# 1_P1.net
KiCad netlist of a schematic drawn in Altium Designer
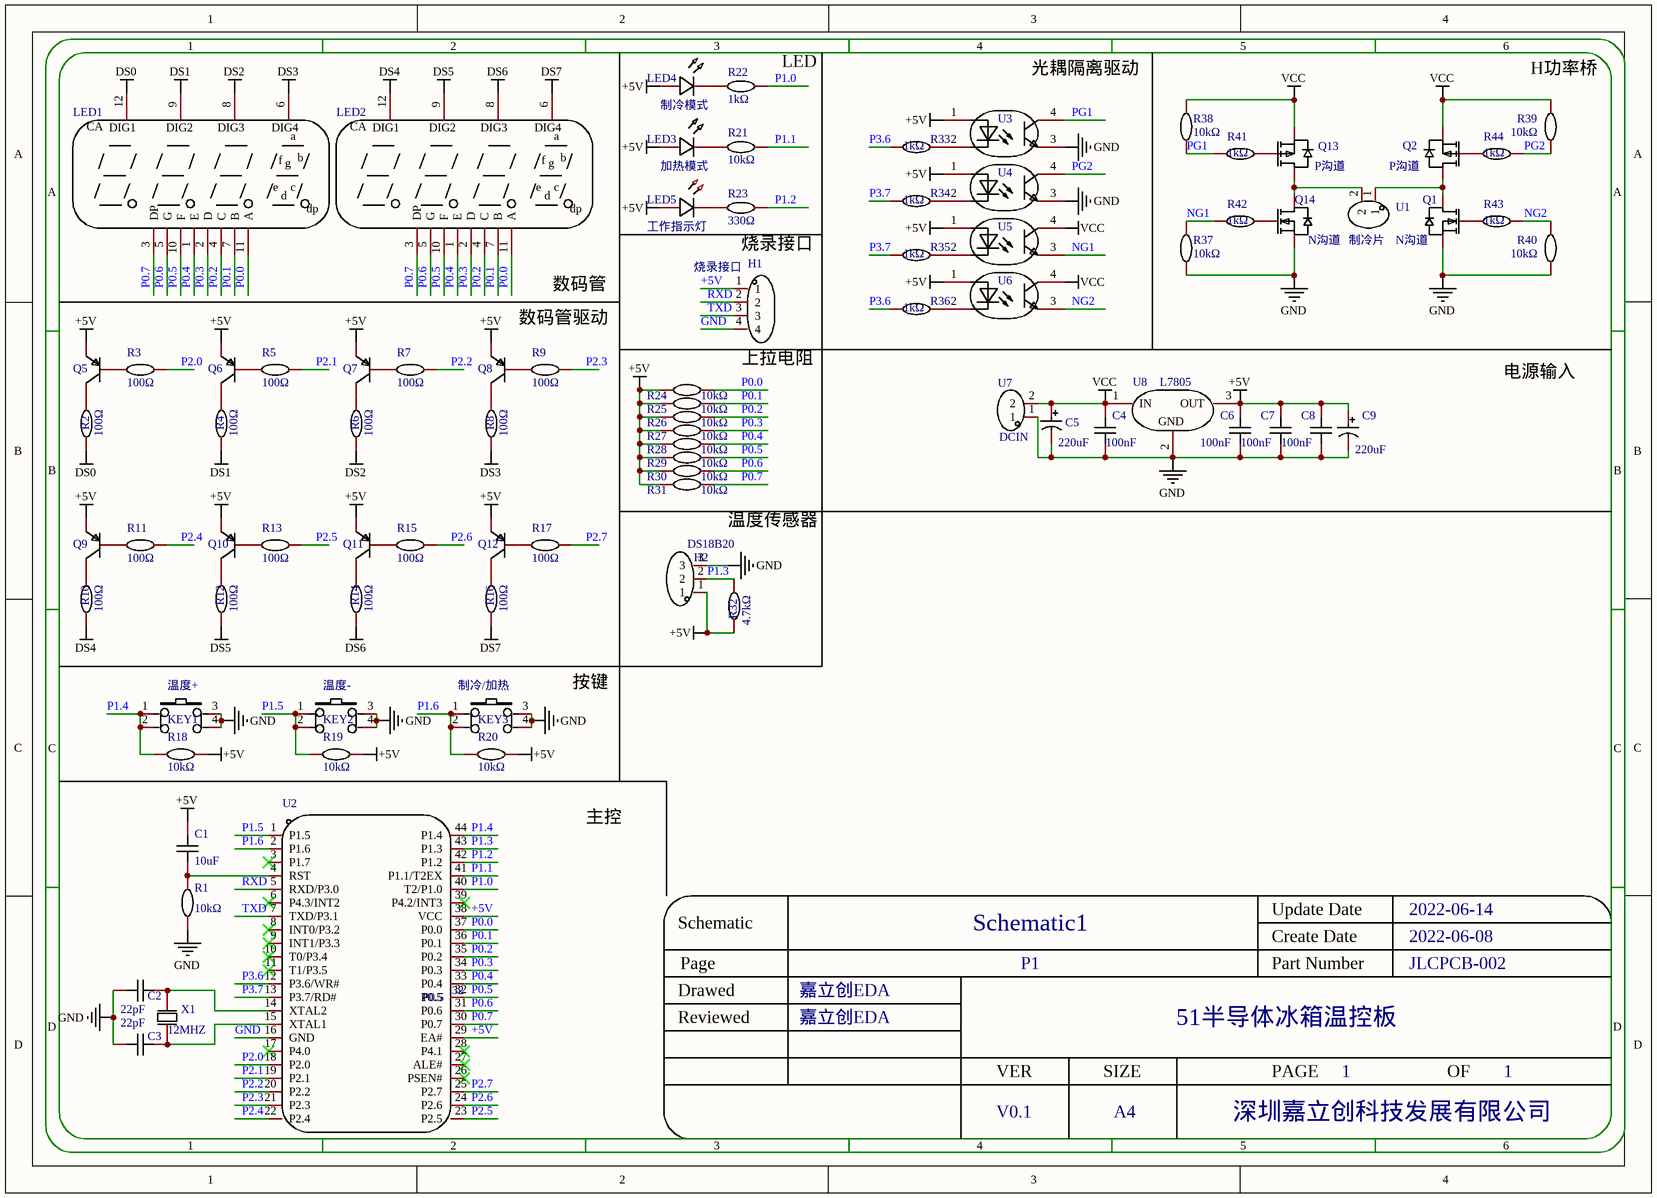
[diagram p0: 1_P1.schdoc]

(export (version "E")
  (design (tool "Eeschema 10.0.6"))
  (components
    (comp (ref "C1")
      (value "10uF")
      (footprint "C0805")
      (description "容值:100nF;精度:±10%;额定电压:50V;温度系数:X7R;")
      (fields (field (name "Comment") "CAP_0805"))
      (libsource (lib "altium-import") (part "root_1_CAP_0805_"))
    )
    (comp (ref "C2")
      (value "22pF")
      (footprint "C0805")
      (description "容值:100nF;精度:±10%;额定电压:50V;温度系数:X7R;")
      (fields (field (name "Comment") "CAP_0805"))
      (libsource (lib "altium-import") (part "root_0_CAP_0805_"))
    )
    (comp (ref "C3")
      (value "22pF")
      (footprint "C0805")
      (description "容值:100nF;精度:±10%;额定电压:50V;温度系数:X7R;")
      (fields (field (name "Comment") "CAP_0805"))
      (libsource (lib "altium-import") (part "root_0_CAP_0805_"))
    )
    (comp (ref "C4")
      (value "C318C362K5G5TA")
      (footprint "CAP-TH_L3.8-W2.5-P5.08-D0.5")
      (fields (field (name "MANUFACTURER") "KEMET(基美)") (field (name "CAPACITANCE") "100nF"))
      (libsource (lib "altium-import") (part "root_1_C318C362K5G5TA_"))
    )
    (comp (ref "C5")
      (value "220uF")
      (footprint "CAP-TH_BD6.3-P2.50-D1.0-FD")
      (description "容值:220uF;精度:±20%;额定电压:10V;电容体直径:6.3mm;电容体长度:7mm;脚间距:2.5mm;纹波电流:-;等效串联电阻:-;工作寿命:1000hrs@105;工作温度:-;")
      (fields
        (field (name "MANUFACTURER") "CapXon(台湾丰宾)")
        (field (name "MANUFACTURER PART") "SK221M010E070A")
      )
      (libsource (lib "altium-import") (part "root_3_SK221M010E070A_"))
    )
    (comp (ref "C6")
      (value "100nF")
      (footprint "C0805")
      (description "容值:100nF;精度:±10%;额定电压:50V;温度系数:X7R;")
      (fields (field (name "Comment") "CAP_0805"))
      (libsource (lib "altium-import") (part "root_1_CAP_0805_"))
    )
    (comp (ref "C7")
      (value "100nF")
      (footprint "C0805")
      (description "容值:100nF;精度:±10%;额定电压:50V;温度系数:X7R;")
      (fields (field (name "Comment") "CAP_0805"))
      (libsource (lib "altium-import") (part "root_1_CAP_0805_"))
    )
    (comp (ref "C8")
      (value "100nF")
      (footprint "C0805")
      (description "容值:100nF;精度:±10%;额定电压:50V;温度系数:X7R;")
      (fields (field (name "Comment") "CAP_0805"))
      (libsource (lib "altium-import") (part "root_1_CAP_0805_"))
    )
    (comp (ref "C9")
      (value "220uF")
      (footprint "CAP-TH_BD6.3-P2.50-D1.0-FD")
      (description "容值:220uF;精度:±20%;额定电压:10V;电容体直径:6.3mm;电容体长度:7mm;脚间距:2.5mm;纹波电流:-;等效串联电阻:-;工作寿命:1000hrs@105;工作温度:-;")
      (fields
        (field (name "MANUFACTURER") "CapXon(台湾丰宾)")
        (field (name "MANUFACTURER PART") "SK221M010E070A")
      )
      (libsource (lib "altium-import") (part "root_3_SK221M010E070A_"))
    )
    (comp (ref "H1")
      (value "烧录接口")
      (footprint "HDR-TH_4P-P2.54-V-F")
      (fields (field (name "NAME") "烧录接口"))
      (libsource (lib "altium-import") (part "root_0_HDR-F_2.54_1x4P_"))
    )
    (comp (ref "H2")
      (value "DS18B20")
      (footprint "HDR-TH_3P-P2.54-V-F")
      (fields (field (name "NAME") "DS18B20"))
      (libsource (lib "altium-import") (part "root_2_HDR-F_2.54_1x3P_"))
    )
    (comp (ref "KEY1")
      (value "温度+")
      (footprint "KEY-SMD_4P-L6.0-W6.0-P4.50")
      (description "触点电流:50mA;额定电压(DC):24V;电路结构:单刀单掷;安装方式:立贴;按钮形状:圆形按钮;带灯:-;开关长度:6mm;开关宽度:6mm;开关高度:5mm;")
      (fields
        (field (name "NAME") "温度+")
        (field (name "MANUFACTURER") "TE Connectivity(美国泰科)")
        (field (name "MANUFACTURER PART") "4-1437565-2")
      )
      (libsource (lib "altium-import") (part "root_0_4-1437565-2_"))
    )
    (comp (ref "KEY2")
      (value "温度-")
      (footprint "KEY-SMD_4P-L6.0-W6.0-P4.50")
      (description "触点电流:50mA;额定电压(DC):24V;电路结构:单刀单掷;安装方式:立贴;按钮形状:圆形按钮;带灯:-;开关长度:6mm;开关宽度:6mm;开关高度:5mm;")
      (fields
        (field (name "NAME") "温度-")
        (field (name "MANUFACTURER") "TE Connectivity(美国泰科)")
        (field (name "MANUFACTURER PART") "4-1437565-2")
      )
      (libsource (lib "altium-import") (part "root_0_4-1437565-2_"))
    )
    (comp (ref "KEY3")
      (value "制冷/加热")
      (footprint "KEY-SMD_4P-L6.0-W6.0-P4.50")
      (description "触点电流:50mA;额定电压(DC):24V;电路结构:单刀单掷;安装方式:立贴;按钮形状:圆形按钮;带灯:-;开关长度:6mm;开关宽度:6mm;开关高度:5mm;")
      (fields
        (field (name "NAME") "制冷/加热")
        (field (name "MANUFACTURER") "TE Connectivity(美国泰科)")
        (field (name "MANUFACTURER PART") "4-1437565-2")
      )
      (libsource (lib "altium-import") (part "root_0_4-1437565-2_"))
    )
    (comp (ref "LED1")
      (value "FJ5461BH 纯红")
      (footprint "LED-SEG-TH_FJ5461AH")
      (description "数码管位数:4;数码管的显示尺寸:0.56''(14.22mm);电路连线类型:阳极(正极);照明颜色:红色;")
      (fields (field (name "MANUFACTURER") "志浩"))
      (libsource (lib "altium-import") (part "root_0_FJ5461BH 纯红_"))
    )
    (comp (ref "LED2")
      (value "FJ5461BH 纯红")
      (footprint "LED-SEG-TH_FJ5461AH")
      (description "数码管位数:4;数码管的显示尺寸:0.56''(14.22mm);电路连线类型:阳极(正极);照明颜色:红色;")
      (fields (field (name "MANUFACTURER") "志浩"))
      (libsource (lib "altium-import") (part "root_0_FJ5461BH 纯红_"))
    )
    (comp (ref "LED3")
      (value "加热模式")
      (footprint "LED-TH_BD3.0-P2.54-FD")
      (fields (field (name "NAME") "加热模式"))
      (libsource (lib "altium-import") (part "root_0_LED_TH-R_3mm_"))
    )
    (comp (ref "LED4")
      (value "制冷模式")
      (footprint "LED-TH_BD3.8-P2.54-FD_BLUE")
      (fields (field (name "NAME") "制冷模式"))
      (libsource (lib "altium-import") (part "root_0_LED_TH-B_3mm_"))
    )
    (comp (ref "LED5")
      (value "工作指示灯")
      (footprint "LED-TH_BD3.0-P2.54-FD")
      (fields (field (name "NAME") "工作指示灯"))
      (libsource (lib "altium-import") (part "root_0_LED_TH-G_3mm_"))
    )
    (comp (ref "Q1")
      (value "N沟道")
      (footprint "TO-220-3_L10.0-W4.5-P2.54-L")
      (fields
        (field (name "NAME") "N沟道")
        (field (name "MANUFACTURER") "CRMICRO(华润微)")
        (field (name "MANUFACTURER PART") "CRST060N10N")
      )
      (libsource (lib "altium-import") (part "root_0_mirrored_CRST060N10N_"))
    )
    (comp (ref "Q2")
      (value "P沟道")
      (footprint "TO-220-3_L10.0-W4.5-P2.54-L")
      (fields
        (field (name "NAME") "P沟道")
        (field (name "MANUFACTURER") "HUASHUO(华朔)")
        (field (name "MANUFACTURER PART") "HSP0115")
      )
      (libsource (lib "altium-import") (part "root_2_HSP0115_"))
    )
    (comp (ref "Q5")
      (value "S8550")
      (footprint "SOT-23-3_L2.9-W1.3-P1.90-LS2.4-BR")
      (fields (field (name "MANUFACTURER") "JSMSEMI(杰盛微)"))
      (libsource (lib "altium-import") (part "root_2_S8550_"))
    )
    (comp (ref "Q6")
      (value "S8550")
      (footprint "SOT-23-3_L2.9-W1.3-P1.90-LS2.4-BR")
      (fields (field (name "MANUFACTURER") "JSMSEMI(杰盛微)"))
      (libsource (lib "altium-import") (part "root_2_S8550_"))
    )
    (comp (ref "Q7")
      (value "S8550")
      (footprint "SOT-23-3_L2.9-W1.3-P1.90-LS2.4-BR")
      (fields (field (name "MANUFACTURER") "JSMSEMI(杰盛微)"))
      (libsource (lib "altium-import") (part "root_2_S8550_"))
    )
    (comp (ref "Q8")
      (value "S8550")
      (footprint "SOT-23-3_L2.9-W1.3-P1.90-LS2.4-BR")
      (fields (field (name "MANUFACTURER") "JSMSEMI(杰盛微)"))
      (libsource (lib "altium-import") (part "root_2_S8550_"))
    )
    (comp (ref "Q9")
      (value "S8550")
      (footprint "SOT-23-3_L2.9-W1.3-P1.90-LS2.4-BR")
      (fields (field (name "MANUFACTURER") "JSMSEMI(杰盛微)"))
      (libsource (lib "altium-import") (part "root_2_S8550_"))
    )
    (comp (ref "Q10")
      (value "S8550")
      (footprint "SOT-23-3_L2.9-W1.3-P1.90-LS2.4-BR")
      (fields (field (name "MANUFACTURER") "JSMSEMI(杰盛微)"))
      (libsource (lib "altium-import") (part "root_2_S8550_"))
    )
    (comp (ref "Q11")
      (value "S8550")
      (footprint "SOT-23-3_L2.9-W1.3-P1.90-LS2.4-BR")
      (fields (field (name "MANUFACTURER") "JSMSEMI(杰盛微)"))
      (libsource (lib "altium-import") (part "root_2_S8550_"))
    )
    (comp (ref "Q12")
      (value "S8550")
      (footprint "SOT-23-3_L2.9-W1.3-P1.90-LS2.4-BR")
      (fields (field (name "MANUFACTURER") "JSMSEMI(杰盛微)"))
      (libsource (lib "altium-import") (part "root_2_S8550_"))
    )
    (comp (ref "Q13")
      (value "P沟道")
      (footprint "TO-220-3_L10.0-W4.5-P2.54-L")
      (fields
        (field (name "NAME") "P沟道")
        (field (name "MANUFACTURER") "HUASHUO(华朔)")
        (field (name "MANUFACTURER PART") "HSP0115")
      )
      (libsource (lib "altium-import") (part "root_2_mirrored_HSP0115_"))
    )
    (comp (ref "Q14")
      (value "N沟道")
      (footprint "TO-220-3_L10.0-W4.5-P2.54-L")
      (fields
        (field (name "NAME") "N沟道")
        (field (name "MANUFACTURER") "CRMICRO(华润微)")
        (field (name "MANUFACTURER PART") "CRST060N10N")
      )
      (libsource (lib "altium-import") (part "root_0_CRST060N10N_"))
    )
    (comp (ref "R1")
      (value "10kΩ")
      (footprint "R0805")
      (description "电阻类型:薄膜电阻;阻值:10kΩ;精度:±0.5%;功率:125mW;温度系数:±25ppm/;最大工作电压:100V;工作温度范围:-55~+155;")
      (fields (field (name "MANUFACTURER") "光颉(Viking)") (field (name "MANUFACTURER PART") "AR05DTCW1002"))
      (libsource (lib "altium-import") (part "root_1_Res_0805_"))
    )
    (comp (ref "R2")
      (value "100Ω")
      (footprint "R0805")
      (description "电阻类型:薄膜电阻;阻值:10kΩ;精度:±0.5%;功率:125mW;温度系数:±25ppm/;最大工作电压:100V;工作温度范围:-55~+155;")
      (fields (field (name "MANUFACTURER") "光颉(Viking)") (field (name "MANUFACTURER PART") "AR05DTCW1002"))
      (libsource (lib "altium-import") (part "root_1_Res_0805_"))
    )
    (comp (ref "R3")
      (value "100Ω")
      (footprint "R0805")
      (description "电阻类型:薄膜电阻;阻值:10kΩ;精度:±0.5%;功率:125mW;温度系数:±25ppm/;最大工作电压:100V;工作温度范围:-55~+155;")
      (fields (field (name "MANUFACTURER") "光颉(Viking)") (field (name "MANUFACTURER PART") "AR05DTCW1002"))
      (libsource (lib "altium-import") (part "root_0_Res_0805_"))
    )
    (comp (ref "R4")
      (value "100Ω")
      (footprint "R0805")
      (description "电阻类型:薄膜电阻;阻值:10kΩ;精度:±0.5%;功率:125mW;温度系数:±25ppm/;最大工作电压:100V;工作温度范围:-55~+155;")
      (fields (field (name "MANUFACTURER") "光颉(Viking)") (field (name "MANUFACTURER PART") "AR05DTCW1002"))
      (libsource (lib "altium-import") (part "root_1_Res_0805_"))
    )
    (comp (ref "R5")
      (value "100Ω")
      (footprint "R0805")
      (description "电阻类型:薄膜电阻;阻值:10kΩ;精度:±0.5%;功率:125mW;温度系数:±25ppm/;最大工作电压:100V;工作温度范围:-55~+155;")
      (fields (field (name "MANUFACTURER") "光颉(Viking)") (field (name "MANUFACTURER PART") "AR05DTCW1002"))
      (libsource (lib "altium-import") (part "root_0_Res_0805_"))
    )
    (comp (ref "R6")
      (value "100Ω")
      (footprint "R0805")
      (description "电阻类型:薄膜电阻;阻值:10kΩ;精度:±0.5%;功率:125mW;温度系数:±25ppm/;最大工作电压:100V;工作温度范围:-55~+155;")
      (fields (field (name "MANUFACTURER") "光颉(Viking)") (field (name "MANUFACTURER PART") "AR05DTCW1002"))
      (libsource (lib "altium-import") (part "root_1_Res_0805_"))
    )
    (comp (ref "R7")
      (value "100Ω")
      (footprint "R0805")
      (description "电阻类型:薄膜电阻;阻值:10kΩ;精度:±0.5%;功率:125mW;温度系数:±25ppm/;最大工作电压:100V;工作温度范围:-55~+155;")
      (fields (field (name "MANUFACTURER") "光颉(Viking)") (field (name "MANUFACTURER PART") "AR05DTCW1002"))
      (libsource (lib "altium-import") (part "root_0_Res_0805_"))
    )
    (comp (ref "R8")
      (value "100Ω")
      (footprint "R0805")
      (description "电阻类型:薄膜电阻;阻值:10kΩ;精度:±0.5%;功率:125mW;温度系数:±25ppm/;最大工作电压:100V;工作温度范围:-55~+155;")
      (fields (field (name "MANUFACTURER") "光颉(Viking)") (field (name "MANUFACTURER PART") "AR05DTCW1002"))
      (libsource (lib "altium-import") (part "root_1_Res_0805_"))
    )
    (comp (ref "R9")
      (value "100Ω")
      (footprint "R0805")
      (description "电阻类型:薄膜电阻;阻值:10kΩ;精度:±0.5%;功率:125mW;温度系数:±25ppm/;最大工作电压:100V;工作温度范围:-55~+155;")
      (fields (field (name "MANUFACTURER") "光颉(Viking)") (field (name "MANUFACTURER PART") "AR05DTCW1002"))
      (libsource (lib "altium-import") (part "root_0_Res_0805_"))
    )
    (comp (ref "R10")
      (value "100Ω")
      (footprint "R0805")
      (description "电阻类型:薄膜电阻;阻值:10kΩ;精度:±0.5%;功率:125mW;温度系数:±25ppm/;最大工作电压:100V;工作温度范围:-55~+155;")
      (fields (field (name "MANUFACTURER") "光颉(Viking)") (field (name "MANUFACTURER PART") "AR05DTCW1002"))
      (libsource (lib "altium-import") (part "root_1_Res_0805_"))
    )
    (comp (ref "R11")
      (value "100Ω")
      (footprint "R0805")
      (description "电阻类型:薄膜电阻;阻值:10kΩ;精度:±0.5%;功率:125mW;温度系数:±25ppm/;最大工作电压:100V;工作温度范围:-55~+155;")
      (fields (field (name "MANUFACTURER") "光颉(Viking)") (field (name "MANUFACTURER PART") "AR05DTCW1002"))
      (libsource (lib "altium-import") (part "root_0_Res_0805_"))
    )
    (comp (ref "R12")
      (value "100Ω")
      (footprint "R0805")
      (description "电阻类型:薄膜电阻;阻值:10kΩ;精度:±0.5%;功率:125mW;温度系数:±25ppm/;最大工作电压:100V;工作温度范围:-55~+155;")
      (fields (field (name "MANUFACTURER") "光颉(Viking)") (field (name "MANUFACTURER PART") "AR05DTCW1002"))
      (libsource (lib "altium-import") (part "root_1_Res_0805_"))
    )
    (comp (ref "R13")
      (value "100Ω")
      (footprint "R0805")
      (description "电阻类型:薄膜电阻;阻值:10kΩ;精度:±0.5%;功率:125mW;温度系数:±25ppm/;最大工作电压:100V;工作温度范围:-55~+155;")
      (fields (field (name "MANUFACTURER") "光颉(Viking)") (field (name "MANUFACTURER PART") "AR05DTCW1002"))
      (libsource (lib "altium-import") (part "root_0_Res_0805_"))
    )
    (comp (ref "R14")
      (value "100Ω")
      (footprint "R0805")
      (description "电阻类型:薄膜电阻;阻值:10kΩ;精度:±0.5%;功率:125mW;温度系数:±25ppm/;最大工作电压:100V;工作温度范围:-55~+155;")
      (fields (field (name "MANUFACTURER") "光颉(Viking)") (field (name "MANUFACTURER PART") "AR05DTCW1002"))
      (libsource (lib "altium-import") (part "root_1_Res_0805_"))
    )
    (comp (ref "R15")
      (value "100Ω")
      (footprint "R0805")
      (description "电阻类型:薄膜电阻;阻值:10kΩ;精度:±0.5%;功率:125mW;温度系数:±25ppm/;最大工作电压:100V;工作温度范围:-55~+155;")
      (fields (field (name "MANUFACTURER") "光颉(Viking)") (field (name "MANUFACTURER PART") "AR05DTCW1002"))
      (libsource (lib "altium-import") (part "root_0_Res_0805_"))
    )
    (comp (ref "R16")
      (value "100Ω")
      (footprint "R0805")
      (description "电阻类型:薄膜电阻;阻值:10kΩ;精度:±0.5%;功率:125mW;温度系数:±25ppm/;最大工作电压:100V;工作温度范围:-55~+155;")
      (fields (field (name "MANUFACTURER") "光颉(Viking)") (field (name "MANUFACTURER PART") "AR05DTCW1002"))
      (libsource (lib "altium-import") (part "root_1_Res_0805_"))
    )
    (comp (ref "R17")
      (value "100Ω")
      (footprint "R0805")
      (description "电阻类型:薄膜电阻;阻值:10kΩ;精度:±0.5%;功率:125mW;温度系数:±25ppm/;最大工作电压:100V;工作温度范围:-55~+155;")
      (fields (field (name "MANUFACTURER") "光颉(Viking)") (field (name "MANUFACTURER PART") "AR05DTCW1002"))
      (libsource (lib "altium-import") (part "root_0_Res_0805_"))
    )
    (comp (ref "R18")
      (value "10kΩ")
      (footprint "R0805")
      (description "电阻类型:薄膜电阻;阻值:10kΩ;精度:±0.5%;功率:125mW;温度系数:±25ppm/;最大工作电压:100V;工作温度范围:-55~+155;")
      (fields (field (name "MANUFACTURER") "光颉(Viking)") (field (name "MANUFACTURER PART") "AR05DTCW1002"))
      (libsource (lib "altium-import") (part "root_0_Res_0805_"))
    )
    (comp (ref "R19")
      (value "10kΩ")
      (footprint "R0805")
      (description "电阻类型:薄膜电阻;阻值:10kΩ;精度:±0.5%;功率:125mW;温度系数:±25ppm/;最大工作电压:100V;工作温度范围:-55~+155;")
      (fields (field (name "MANUFACTURER") "光颉(Viking)") (field (name "MANUFACTURER PART") "AR05DTCW1002"))
      (libsource (lib "altium-import") (part "root_0_Res_0805_"))
    )
    (comp (ref "R20")
      (value "10kΩ")
      (footprint "R0805")
      (description "电阻类型:薄膜电阻;阻值:10kΩ;精度:±0.5%;功率:125mW;温度系数:±25ppm/;最大工作电压:100V;工作温度范围:-55~+155;")
      (fields (field (name "MANUFACTURER") "光颉(Viking)") (field (name "MANUFACTURER PART") "AR05DTCW1002"))
      (libsource (lib "altium-import") (part "root_0_Res_0805_"))
    )
    (comp (ref "R21")
      (value "10kΩ")
      (footprint "R0805")
      (description "电阻类型:薄膜电阻;阻值:10kΩ;精度:±0.5%;功率:125mW;温度系数:±25ppm/;最大工作电压:100V;工作温度范围:-55~+155;")
      (fields (field (name "MANUFACTURER") "光颉(Viking)") (field (name "MANUFACTURER PART") "AR05DTCW1002"))
      (libsource (lib "altium-import") (part "root_2_Res_0805_"))
    )
    (comp (ref "R22")
      (value "1kΩ")
      (footprint "R0805")
      (description "电阻类型:薄膜电阻;阻值:10kΩ;精度:±0.5%;功率:125mW;温度系数:±25ppm/;最大工作电压:100V;工作温度范围:-55~+155;")
      (fields (field (name "MANUFACTURER") "光颉(Viking)") (field (name "MANUFACTURER PART") "AR05DTCW1002"))
      (libsource (lib "altium-import") (part "root_2_Res_0805_"))
    )
    (comp (ref "R23")
      (value "330Ω")
      (footprint "R0805")
      (description "电阻类型:薄膜电阻;阻值:10kΩ;精度:±0.5%;功率:125mW;温度系数:±25ppm/;最大工作电压:100V;工作温度范围:-55~+155;")
      (fields (field (name "MANUFACTURER") "光颉(Viking)") (field (name "MANUFACTURER PART") "AR05DTCW1002"))
      (libsource (lib "altium-import") (part "root_2_Res_0805_"))
    )
    (comp (ref "R24")
      (value "10kΩ")
      (footprint "R0805")
      (description "电阻类型:薄膜电阻;阻值:10kΩ;精度:±0.5%;功率:125mW;温度系数:±25ppm/;最大工作电压:100V;工作温度范围:-55~+155;")
      (fields (field (name "MANUFACTURER") "光颉(Viking)") (field (name "MANUFACTURER PART") "AR05DTCW1002"))
      (libsource (lib "altium-import") (part "root_0_Res_0805_"))
    )
    (comp (ref "R25")
      (value "10kΩ")
      (footprint "R0805")
      (description "电阻类型:薄膜电阻;阻值:10kΩ;精度:±0.5%;功率:125mW;温度系数:±25ppm/;最大工作电压:100V;工作温度范围:-55~+155;")
      (fields (field (name "MANUFACTURER") "光颉(Viking)") (field (name "MANUFACTURER PART") "AR05DTCW1002"))
      (libsource (lib "altium-import") (part "root_0_Res_0805_"))
    )
    (comp (ref "R26")
      (value "10kΩ")
      (footprint "R0805")
      (description "电阻类型:薄膜电阻;阻值:10kΩ;精度:±0.5%;功率:125mW;温度系数:±25ppm/;最大工作电压:100V;工作温度范围:-55~+155;")
      (fields (field (name "MANUFACTURER") "光颉(Viking)") (field (name "MANUFACTURER PART") "AR05DTCW1002"))
      (libsource (lib "altium-import") (part "root_0_Res_0805_"))
    )
    (comp (ref "R27")
      (value "10kΩ")
      (footprint "R0805")
      (description "电阻类型:薄膜电阻;阻值:10kΩ;精度:±0.5%;功率:125mW;温度系数:±25ppm/;最大工作电压:100V;工作温度范围:-55~+155;")
      (fields (field (name "MANUFACTURER") "光颉(Viking)") (field (name "MANUFACTURER PART") "AR05DTCW1002"))
      (libsource (lib "altium-import") (part "root_0_Res_0805_"))
    )
    (comp (ref "R28")
      (value "10kΩ")
      (footprint "R0805")
      (description "电阻类型:薄膜电阻;阻值:10kΩ;精度:±0.5%;功率:125mW;温度系数:±25ppm/;最大工作电压:100V;工作温度范围:-55~+155;")
      (fields (field (name "MANUFACTURER") "光颉(Viking)") (field (name "MANUFACTURER PART") "AR05DTCW1002"))
      (libsource (lib "altium-import") (part "root_0_Res_0805_"))
    )
    (comp (ref "R29")
      (value "10kΩ")
      (footprint "R0805")
      (description "电阻类型:薄膜电阻;阻值:10kΩ;精度:±0.5%;功率:125mW;温度系数:±25ppm/;最大工作电压:100V;工作温度范围:-55~+155;")
      (fields (field (name "MANUFACTURER") "光颉(Viking)") (field (name "MANUFACTURER PART") "AR05DTCW1002"))
      (libsource (lib "altium-import") (part "root_0_Res_0805_"))
    )
    (comp (ref "R30")
      (value "10kΩ")
      (footprint "R0805")
      (description "电阻类型:薄膜电阻;阻值:10kΩ;精度:±0.5%;功率:125mW;温度系数:±25ppm/;最大工作电压:100V;工作温度范围:-55~+155;")
      (fields (field (name "MANUFACTURER") "光颉(Viking)") (field (name "MANUFACTURER PART") "AR05DTCW1002"))
      (libsource (lib "altium-import") (part "root_0_Res_0805_"))
    )
    (comp (ref "R31")
      (value "10kΩ")
      (footprint "R0805")
      (description "电阻类型:薄膜电阻;阻值:10kΩ;精度:±0.5%;功率:125mW;温度系数:±25ppm/;最大工作电压:100V;工作温度范围:-55~+155;")
      (fields (field (name "MANUFACTURER") "光颉(Viking)") (field (name "MANUFACTURER PART") "AR05DTCW1002"))
      (libsource (lib "altium-import") (part "root_0_Res_0805_"))
    )
    (comp (ref "R32")
      (value "4.7kΩ")
      (footprint "R0805")
      (description "电阻类型:薄膜电阻;阻值:10kΩ;精度:±0.5%;功率:125mW;温度系数:±25ppm/;最大工作电压:100V;工作温度范围:-55~+155;")
      (fields (field (name "MANUFACTURER") "光颉(Viking)") (field (name "MANUFACTURER PART") "AR05DTCW1002"))
      (libsource (lib "altium-import") (part "root_1_Res_0805_"))
    )
    (comp (ref "R33")
      (value "1kΩ")
      (footprint "R0805")
      (description "电阻类型:薄膜电阻;阻值:10kΩ;精度:±0.5%;功率:125mW;温度系数:±25ppm/;最大工作电压:100V;工作温度范围:-55~+155;")
      (fields (field (name "MANUFACTURER") "光颉(Viking)") (field (name "MANUFACTURER PART") "AR05DTCW1002"))
      (libsource (lib "altium-import") (part "root_0_Res_0805_"))
    )
    (comp (ref "R34")
      (value "1kΩ")
      (footprint "R0805")
      (description "电阻类型:薄膜电阻;阻值:10kΩ;精度:±0.5%;功率:125mW;温度系数:±25ppm/;最大工作电压:100V;工作温度范围:-55~+155;")
      (fields (field (name "MANUFACTURER") "光颉(Viking)") (field (name "MANUFACTURER PART") "AR05DTCW1002"))
      (libsource (lib "altium-import") (part "root_0_Res_0805_"))
    )
    (comp (ref "R35")
      (value "1kΩ")
      (footprint "R0805")
      (description "电阻类型:薄膜电阻;阻值:10kΩ;精度:±0.5%;功率:125mW;温度系数:±25ppm/;最大工作电压:100V;工作温度范围:-55~+155;")
      (fields (field (name "MANUFACTURER") "光颉(Viking)") (field (name "MANUFACTURER PART") "AR05DTCW1002"))
      (libsource (lib "altium-import") (part "root_0_Res_0805_"))
    )
    (comp (ref "R36")
      (value "1kΩ")
      (footprint "R0805")
      (description "电阻类型:薄膜电阻;阻值:10kΩ;精度:±0.5%;功率:125mW;温度系数:±25ppm/;最大工作电压:100V;工作温度范围:-55~+155;")
      (fields (field (name "MANUFACTURER") "光颉(Viking)") (field (name "MANUFACTURER PART") "AR05DTCW1002"))
      (libsource (lib "altium-import") (part "root_0_Res_0805_"))
    )
    (comp (ref "R37")
      (value "10kΩ")
      (footprint "R0805")
      (description "电阻类型:薄膜电阻;阻值:10kΩ;精度:±0.5%;功率:125mW;温度系数:±25ppm/;最大工作电压:100V;工作温度范围:-55~+155;")
      (fields (field (name "MANUFACTURER") "光颉(Viking)") (field (name "MANUFACTURER PART") "AR05DTCW1002"))
      (libsource (lib "altium-import") (part "root_1_Res_0805_"))
    )
    (comp (ref "R38")
      (value "10kΩ")
      (footprint "R0805")
      (description "电阻类型:薄膜电阻;阻值:10kΩ;精度:±0.5%;功率:125mW;温度系数:±25ppm/;最大工作电压:100V;工作温度范围:-55~+155;")
      (fields (field (name "MANUFACTURER") "光颉(Viking)") (field (name "MANUFACTURER PART") "AR05DTCW1002"))
      (libsource (lib "altium-import") (part "root_1_Res_0805_"))
    )
    (comp (ref "R39")
      (value "10kΩ")
      (footprint "R0805")
      (description "电阻类型:薄膜电阻;阻值:10kΩ;精度:±0.5%;功率:125mW;温度系数:±25ppm/;最大工作电压:100V;工作温度范围:-55~+155;")
      (fields (field (name "MANUFACTURER") "光颉(Viking)") (field (name "MANUFACTURER PART") "AR05DTCW1002"))
      (libsource (lib "altium-import") (part "root_1_Res_0805_"))
    )
    (comp (ref "R40")
      (value "10kΩ")
      (footprint "R0805")
      (description "电阻类型:薄膜电阻;阻值:10kΩ;精度:±0.5%;功率:125mW;温度系数:±25ppm/;最大工作电压:100V;工作温度范围:-55~+155;")
      (fields (field (name "MANUFACTURER") "光颉(Viking)") (field (name "MANUFACTURER PART") "AR05DTCW1002"))
      (libsource (lib "altium-import") (part "root_1_Res_0805_"))
    )
    (comp (ref "R41")
      (value "1kΩ")
      (footprint "R0805")
      (description "电阻类型:薄膜电阻;阻值:10kΩ;精度:±0.5%;功率:125mW;温度系数:±25ppm/;最大工作电压:100V;工作温度范围:-55~+155;")
      (fields (field (name "MANUFACTURER") "光颉(Viking)") (field (name "MANUFACTURER PART") "AR05DTCW1002"))
      (libsource (lib "altium-import") (part "root_0_Res_0805_"))
    )
    (comp (ref "R42")
      (value "1kΩ")
      (footprint "R0805")
      (description "电阻类型:薄膜电阻;阻值:10kΩ;精度:±0.5%;功率:125mW;温度系数:±25ppm/;最大工作电压:100V;工作温度范围:-55~+155;")
      (fields (field (name "MANUFACTURER") "光颉(Viking)") (field (name "MANUFACTURER PART") "AR05DTCW1002"))
      (libsource (lib "altium-import") (part "root_0_Res_0805_"))
    )
    (comp (ref "R43")
      (value "1kΩ")
      (footprint "R0805")
      (description "电阻类型:薄膜电阻;阻值:10kΩ;精度:±0.5%;功率:125mW;温度系数:±25ppm/;最大工作电压:100V;工作温度范围:-55~+155;")
      (fields (field (name "MANUFACTURER") "光颉(Viking)") (field (name "MANUFACTURER PART") "AR05DTCW1002"))
      (libsource (lib "altium-import") (part "root_0_Res_0805_"))
    )
    (comp (ref "R44")
      (value "1kΩ")
      (footprint "R0805")
      (description "电阻类型:薄膜电阻;阻值:10kΩ;精度:±0.5%;功率:125mW;温度系数:±25ppm/;最大工作电压:100V;工作温度范围:-55~+155;")
      (fields (field (name "MANUFACTURER") "光颉(Viking)") (field (name "MANUFACTURER PART") "AR05DTCW1002"))
      (libsource (lib "altium-import") (part "root_0_Res_0805_"))
    )
    (comp (ref "U1")
      (value "制冷片")
      (footprint "CONN-TH_P5.00_KF301-5.0-2P")
      (description "间距:5mm;排数:1;每排PIN数:2;安装方式:直针;额定电流:17A;额定电压:250V;线规 - AWG:14~22;线规 - mm?:1.5;工作温度范围:-30~+120;颜色:蓝色;")
      (fields
        (field (name "NAME") "制冷片")
        (field (name "MANUFACTURER") "KEFA(科发)")
        (field (name "MANUFACTURER PART") "KF301-5.0-2P")
      )
      (libsource (lib "altium-import") (part "root_3_KF301-5.0-2P_"))
    )
    (comp (ref "U2")
      (value "STC89C52-35I-LQFP44")
      (footprint "LQFP-44_L10.0-W10.0-P0.80-LS12.0-BL")
      (description "STC89C52   LQFP44封装")
      (fields
        (field (name "MANUFACTURER") "STC(宏晶)")
        (field (name "NAME") "P0.5")
        (field (name "NUMBER") "32")
      )
      (libsource (lib "altium-import") (part "root_0_STC89C52-35I-LQFP44_"))
    )
    (comp (ref "U3")
      (value "PC817B_1")
      (footprint "OPTO-SMD-4_L4.6-W6.5-P2.54-LS10.3-TL")
      (fields (field (name "MANUFACTURER") "GOODWORK(固得沃克)") (field (name "MANUFACTURER PART") "PC817B"))
      (libsource (lib "altium-import") (part "root_0_PC817B_1_"))
    )
    (comp (ref "U4")
      (value "PC817B_1")
      (footprint "OPTO-SMD-4_L4.6-W6.5-P2.54-LS10.3-TL")
      (fields (field (name "MANUFACTURER") "GOODWORK(固得沃克)") (field (name "MANUFACTURER PART") "PC817B"))
      (libsource (lib "altium-import") (part "root_0_PC817B_1_"))
    )
    (comp (ref "U5")
      (value "PC817B_1")
      (footprint "OPTO-SMD-4_L4.6-W6.5-P2.54-LS10.3-TL")
      (fields (field (name "MANUFACTURER") "GOODWORK(固得沃克)") (field (name "MANUFACTURER PART") "PC817B"))
      (libsource (lib "altium-import") (part "root_0_PC817B_1_"))
    )
    (comp (ref "U6")
      (value "PC817B_1")
      (footprint "OPTO-SMD-4_L4.6-W6.5-P2.54-LS10.3-TL")
      (fields (field (name "MANUFACTURER") "GOODWORK(固得沃克)") (field (name "MANUFACTURER PART") "PC817B"))
      (libsource (lib "altium-import") (part "root_0_PC817B_1_"))
    )
    (comp (ref "U7")
      (value "DCIN")
      (footprint "CONN-TH_P5.00_KF301-5.0-2P")
      (description "间距:5mm;排数:1;每排PIN数:2;安装方式:直针;额定电流:17A;额定电压:250V;线规 - AWG:14~22;线规 - mm?:1.5;工作温度范围:-30~+120;颜色:蓝色;")
      (fields
        (field (name "NAME") "DCIN")
        (field (name "MANUFACTURER") "KEFA(科发)")
        (field (name "MANUFACTURER PART") "KF301-5.0-2P")
      )
      (libsource (lib "altium-import") (part "root_2_KF301-5.0-2P_"))
    )
    (comp (ref "U8")
      (value "L7805")
      (footprint "TO-220-3_L10.0-W4.5-P2.54-L")
      (description "输出类型:-;")
      (fields
        (field (name "NAME") "L7805")
        (field (name "MANUFACTURER") "HGC(华冠)")
        (field (name "MANUFACTURER PART") "L7805CV")
      )
      (libsource (lib "altium-import") (part "root_0_L7805CV_"))
    )
    (comp (ref "X1")
      (value "12MHZ")
      (footprint "HC-49US_L11.5-W4.5-P4.88")
      (description "晶振类型:-;频率:-;频率公差:-;频率稳定度:-;负载电容:-;工作温度:-;")
      (fields
        (field (name "MANUFACTURER") "TAITIEN(泰艺电子)")
        (field (name "MANUFACTURER PART") "XIHCCCNANF-11.0592")
      )
      (libsource (lib "altium-import") (part "root_1_XIHCCCNANF-11.0592_"))
    )
  )
  (nets
    (net (code "1") (name "+5V") (class "Default")
      (node (ref "C1") (pin "2") (pinfunction "2_2") (pintype "passive"))
      (node (ref "C6") (pin "2") (pinfunction "2_2") (pintype "passive"))
      (node (ref "C7") (pin "2") (pinfunction "2_2") (pintype "passive"))
      (node (ref "C8") (pin "2") (pinfunction "2_2") (pintype "passive"))
      (node (ref "C9") (pin "1") (pinfunction "1_1") (pintype "passive"))
      (node (ref "H1") (pin "1") (pinfunction "1_1") (pintype "passive"))
      (node (ref "H2") (pin "1") (pinfunction "1_1") (pintype "passive"))
      (node (ref "LED3") (pin "1") (pinfunction "C_1") (pintype "passive"))
      (node (ref "LED4") (pin "1") (pinfunction "C_1") (pintype "passive"))
      (node (ref "LED5") (pin "1") (pinfunction "C_1") (pintype "passive"))
      (node (ref "Q10") (pin "2") (pinfunction "E_2") (pintype "passive"))
      (node (ref "Q11") (pin "2") (pinfunction "E_2") (pintype "passive"))
      (node (ref "Q12") (pin "2") (pinfunction "E_2") (pintype "passive"))
      (node (ref "Q5") (pin "2") (pinfunction "E_2") (pintype "passive"))
      (node (ref "Q6") (pin "2") (pinfunction "E_2") (pintype "passive"))
      (node (ref "Q7") (pin "2") (pinfunction "E_2") (pintype "passive"))
      (node (ref "Q8") (pin "2") (pinfunction "E_2") (pintype "passive"))
      (node (ref "Q9") (pin "2") (pinfunction "E_2") (pintype "passive"))
      (node (ref "R18") (pin "2") (pinfunction "2_2") (pintype "passive"))
      (node (ref "R19") (pin "2") (pinfunction "2_2") (pintype "passive"))
      (node (ref "R20") (pin "2") (pinfunction "2_2") (pintype "passive"))
      (node (ref "R24") (pin "1") (pinfunction "1_1") (pintype "passive"))
      (node (ref "R25") (pin "1") (pinfunction "1_1") (pintype "passive"))
      (node (ref "R26") (pin "1") (pinfunction "1_1") (pintype "passive"))
      (node (ref "R27") (pin "1") (pinfunction "1_1") (pintype "passive"))
      (node (ref "R28") (pin "1") (pinfunction "1_1") (pintype "passive"))
      (node (ref "R29") (pin "1") (pinfunction "1_1") (pintype "passive"))
      (node (ref "R30") (pin "1") (pinfunction "1_1") (pintype "passive"))
      (node (ref "R31") (pin "1") (pinfunction "1_1") (pintype "passive"))
      (node (ref "R32") (pin "1") (pinfunction "1_1") (pintype "passive"))
      (node (ref "U2") (pin "29") (pinfunction "EA#_29") (pintype "passive"))
      (node (ref "U2") (pin "38") (pinfunction "VCC_38") (pintype "passive"))
      (node (ref "U3") (pin "1") (pinfunction "1_1") (pintype "passive"))
      (node (ref "U4") (pin "1") (pinfunction "1_1") (pintype "passive"))
      (node (ref "U5") (pin "1") (pinfunction "1_1") (pintype "passive"))
      (node (ref "U6") (pin "1") (pinfunction "1_1") (pintype "passive"))
      (node (ref "U8") (pin "3") (pinfunction "OUT_3") (pintype "passive"))
    )
    (net (code "2") (name "/NG1") (class "Default")
      (node (ref "R37") (pin "2") (pinfunction "2_2") (pintype "passive"))
      (node (ref "R42") (pin "1") (pinfunction "1_1") (pintype "passive"))
      (node (ref "U5") (pin "3") (pinfunction "3_3") (pintype "passive"))
    )
    (net (code "3") (name "/NG2") (class "Default")
      (node (ref "R40") (pin "2") (pinfunction "2_2") (pintype "passive"))
      (node (ref "R43") (pin "2") (pinfunction "2_2") (pintype "passive"))
      (node (ref "U6") (pin "3") (pinfunction "3_3") (pintype "passive"))
    )
    (net (code "4") (name "/P0.0") (class "Default")
      (node (ref "LED1") (pin "11") (pinfunction "A_11") (pintype "passive"))
      (node (ref "LED2") (pin "11") (pinfunction "A_11") (pintype "passive"))
      (node (ref "R24") (pin "2") (pinfunction "2_2") (pintype "passive"))
      (node (ref "U2") (pin "37") (pinfunction "P0.0_37") (pintype "passive"))
    )
    (net (code "5") (name "/P0.1") (class "Default")
      (node (ref "LED1") (pin "7") (pinfunction "B_7") (pintype "passive"))
      (node (ref "LED2") (pin "7") (pinfunction "B_7") (pintype "passive"))
      (node (ref "R25") (pin "2") (pinfunction "2_2") (pintype "passive"))
      (node (ref "U2") (pin "36") (pinfunction "P0.1_36") (pintype "passive"))
    )
    (net (code "6") (name "/P0.2") (class "Default")
      (node (ref "LED1") (pin "4") (pinfunction "C_4") (pintype "passive"))
      (node (ref "LED2") (pin "4") (pinfunction "C_4") (pintype "passive"))
      (node (ref "R26") (pin "2") (pinfunction "2_2") (pintype "passive"))
      (node (ref "U2") (pin "35") (pinfunction "P0.2_35") (pintype "passive"))
    )
    (net (code "7") (name "/P0.3") (class "Default")
      (node (ref "LED1") (pin "2") (pinfunction "D_2") (pintype "passive"))
      (node (ref "LED2") (pin "2") (pinfunction "D_2") (pintype "passive"))
      (node (ref "R27") (pin "2") (pinfunction "2_2") (pintype "passive"))
      (node (ref "U2") (pin "34") (pinfunction "P0.3_34") (pintype "passive"))
    )
    (net (code "8") (name "/P0.4") (class "Default")
      (node (ref "LED1") (pin "1") (pinfunction "E_1") (pintype "passive"))
      (node (ref "LED2") (pin "1") (pinfunction "E_1") (pintype "passive"))
      (node (ref "R28") (pin "2") (pinfunction "2_2") (pintype "passive"))
      (node (ref "U2") (pin "33") (pinfunction "P0.4_33") (pintype "passive"))
    )
    (net (code "9") (name "/P0.5") (class "Default")
      (node (ref "LED1") (pin "10") (pinfunction "F_10") (pintype "passive"))
      (node (ref "LED2") (pin "10") (pinfunction "F_10") (pintype "passive"))
      (node (ref "R29") (pin "2") (pinfunction "2_2") (pintype "passive"))
      (node (ref "U2") (pin "32") (pinfunction "P0.5_32") (pintype "passive"))
    )
    (net (code "10") (name "/P0.6") (class "Default")
      (node (ref "LED1") (pin "5") (pinfunction "G_5") (pintype "passive"))
      (node (ref "LED2") (pin "5") (pinfunction "G_5") (pintype "passive"))
      (node (ref "R30") (pin "2") (pinfunction "2_2") (pintype "passive"))
      (node (ref "U2") (pin "31") (pinfunction "P0.6_31") (pintype "passive"))
    )
    (net (code "11") (name "/P0.7") (class "Default")
      (node (ref "LED1") (pin "3") (pinfunction "DP_3") (pintype "passive"))
      (node (ref "LED2") (pin "3") (pinfunction "DP_3") (pintype "passive"))
      (node (ref "R31") (pin "2") (pinfunction "2_2") (pintype "passive"))
      (node (ref "U2") (pin "30") (pinfunction "P0.7_30") (pintype "passive"))
    )
    (net (code "12") (name "/P1.0") (class "Default")
      (node (ref "R22") (pin "1") (pinfunction "1_1") (pintype "passive"))
      (node (ref "U2") (pin "40") (pinfunction "T2/P1.0_40") (pintype "passive"))
    )
    (net (code "13") (name "/P1.1") (class "Default")
      (node (ref "R21") (pin "1") (pinfunction "1_1") (pintype "passive"))
      (node (ref "U2") (pin "41") (pinfunction "P1.1/T2EX_41") (pintype "passive"))
    )
    (net (code "14") (name "/P1.2") (class "Default")
      (node (ref "R23") (pin "1") (pinfunction "1_1") (pintype "passive"))
      (node (ref "U2") (pin "42") (pinfunction "P1.2_42") (pintype "passive"))
    )
    (net (code "15") (name "/P1.3") (class "Default")
      (node (ref "H2") (pin "2") (pinfunction "2_2") (pintype "passive"))
      (node (ref "R32") (pin "2") (pinfunction "2_2") (pintype "passive"))
      (node (ref "U2") (pin "43") (pinfunction "P1.3_43") (pintype "passive"))
    )
    (net (code "16") (name "/P1.4") (class "Default")
      (node (ref "KEY1") (pin "1") (pinfunction "1_1") (pintype "passive"))
      (node (ref "KEY1") (pin "2") (pinfunction "2_2") (pintype "passive"))
      (node (ref "R18") (pin "1") (pinfunction "1_1") (pintype "passive"))
      (node (ref "U2") (pin "44") (pinfunction "P1.4_44") (pintype "passive"))
    )
    (net (code "17") (name "/P1.5") (class "Default")
      (node (ref "KEY2") (pin "1") (pinfunction "1_1") (pintype "passive"))
      (node (ref "KEY2") (pin "2") (pinfunction "2_2") (pintype "passive"))
      (node (ref "R19") (pin "1") (pinfunction "1_1") (pintype "passive"))
      (node (ref "U2") (pin "1") (pinfunction "P1.5_1") (pintype "passive"))
    )
    (net (code "18") (name "/P1.6") (class "Default")
      (node (ref "KEY3") (pin "1") (pinfunction "1_1") (pintype "passive"))
      (node (ref "KEY3") (pin "2") (pinfunction "2_2") (pintype "passive"))
      (node (ref "R20") (pin "1") (pinfunction "1_1") (pintype "passive"))
      (node (ref "U2") (pin "2") (pinfunction "P1.6_2") (pintype "passive"))
    )
    (net (code "19") (name "/P2.0") (class "Default")
      (node (ref "R3") (pin "2") (pinfunction "2_2") (pintype "passive"))
      (node (ref "U2") (pin "18") (pinfunction "P2.0_18") (pintype "passive"))
    )
    (net (code "20") (name "/P2.1") (class "Default")
      (node (ref "R5") (pin "2") (pinfunction "2_2") (pintype "passive"))
      (node (ref "U2") (pin "19") (pinfunction "P2.1_19") (pintype "passive"))
    )
    (net (code "21") (name "/P2.2") (class "Default")
      (node (ref "R7") (pin "2") (pinfunction "2_2") (pintype "passive"))
      (node (ref "U2") (pin "20") (pinfunction "P2.2_20") (pintype "passive"))
    )
    (net (code "22") (name "/P2.3") (class "Default")
      (node (ref "R9") (pin "2") (pinfunction "2_2") (pintype "passive"))
      (node (ref "U2") (pin "21") (pinfunction "P2.3_21") (pintype "passive"))
    )
    (net (code "23") (name "/P2.4") (class "Default")
      (node (ref "R11") (pin "2") (pinfunction "2_2") (pintype "passive"))
      (node (ref "U2") (pin "22") (pinfunction "P2.4_22") (pintype "passive"))
    )
    (net (code "24") (name "/P2.5") (class "Default")
      (node (ref "R13") (pin "2") (pinfunction "2_2") (pintype "passive"))
      (node (ref "U2") (pin "23") (pinfunction "P2.5_23") (pintype "passive"))
    )
    (net (code "25") (name "/P2.6") (class "Default")
      (node (ref "R15") (pin "2") (pinfunction "2_2") (pintype "passive"))
      (node (ref "U2") (pin "24") (pinfunction "P2.6_24") (pintype "passive"))
    )
    (net (code "26") (name "/P2.7") (class "Default")
      (node (ref "R17") (pin "2") (pinfunction "2_2") (pintype "passive"))
      (node (ref "U2") (pin "25") (pinfunction "P2.7_25") (pintype "passive"))
    )
    (net (code "27") (name "/P3.6") (class "Default")
      (node (ref "R33") (pin "1") (pinfunction "1_1") (pintype "passive"))
      (node (ref "R36") (pin "1") (pinfunction "1_1") (pintype "passive"))
      (node (ref "U2") (pin "12") (pinfunction "P3.6/WR#_12") (pintype "passive"))
    )
    (net (code "28") (name "/P3.7") (class "Default")
      (node (ref "R34") (pin "1") (pinfunction "1_1") (pintype "passive"))
      (node (ref "R35") (pin "1") (pinfunction "1_1") (pintype "passive"))
      (node (ref "U2") (pin "13") (pinfunction "P3.7/RD#_13") (pintype "passive"))
    )
    (net (code "29") (name "/PG1") (class "Default")
      (node (ref "R38") (pin "1") (pinfunction "1_1") (pintype "passive"))
      (node (ref "R41") (pin "1") (pinfunction "1_1") (pintype "passive"))
      (node (ref "U3") (pin "4") (pinfunction "4_4") (pintype "passive"))
    )
    (net (code "30") (name "/PG2") (class "Default")
      (node (ref "R39") (pin "1") (pinfunction "1_1") (pintype "passive"))
      (node (ref "R44") (pin "2") (pinfunction "2_2") (pintype "passive"))
      (node (ref "U4") (pin "4") (pinfunction "4_4") (pintype "passive"))
    )
    (net (code "31") (name "/RXD") (class "Default")
      (node (ref "H1") (pin "2") (pinfunction "2_2") (pintype "passive"))
      (node (ref "U2") (pin "5") (pinfunction "RXD/P3.0_5") (pintype "passive"))
    )
    (net (code "32") (name "/TXD") (class "Default")
      (node (ref "H1") (pin "3") (pinfunction "3_3") (pintype "passive"))
      (node (ref "U2") (pin "7") (pinfunction "TXD/P3.1_7") (pintype "passive"))
    )
    (net (code "33") (name "DS0") (class "Default")
      (node (ref "LED1") (pin "12") (pinfunction "DIG1_12") (pintype "passive"))
      (node (ref "R2") (pin "1") (pinfunction "1_1") (pintype "passive"))
    )
    (net (code "34") (name "DS1") (class "Default")
      (node (ref "LED1") (pin "9") (pinfunction "DIG2_9") (pintype "passive"))
      (node (ref "R4") (pin "1") (pinfunction "1_1") (pintype "passive"))
    )
    (net (code "35") (name "DS2") (class "Default")
      (node (ref "LED1") (pin "8") (pinfunction "DIG3_8") (pintype "passive"))
      (node (ref "R6") (pin "1") (pinfunction "1_1") (pintype "passive"))
    )
    (net (code "36") (name "DS3") (class "Default")
      (node (ref "LED1") (pin "6") (pinfunction "DIG4_6") (pintype "passive"))
      (node (ref "R8") (pin "1") (pinfunction "1_1") (pintype "passive"))
    )
    (net (code "37") (name "DS4") (class "Default")
      (node (ref "LED2") (pin "12") (pinfunction "DIG1_12") (pintype "passive"))
      (node (ref "R10") (pin "1") (pinfunction "1_1") (pintype "passive"))
    )
    (net (code "38") (name "DS5") (class "Default")
      (node (ref "LED2") (pin "9") (pinfunction "DIG2_9") (pintype "passive"))
      (node (ref "R12") (pin "1") (pinfunction "1_1") (pintype "passive"))
    )
    (net (code "39") (name "DS6") (class "Default")
      (node (ref "LED2") (pin "8") (pinfunction "DIG3_8") (pintype "passive"))
      (node (ref "R14") (pin "1") (pinfunction "1_1") (pintype "passive"))
    )
    (net (code "40") (name "DS7") (class "Default")
      (node (ref "LED2") (pin "6") (pinfunction "DIG4_6") (pintype "passive"))
      (node (ref "R16") (pin "1") (pinfunction "1_1") (pintype "passive"))
    )
    (net (code "41") (name "GND") (class "Default")
      (node (ref "C2") (pin "1") (pinfunction "1_1") (pintype "passive"))
      (node (ref "C3") (pin "1") (pinfunction "1_1") (pintype "passive"))
      (node (ref "C4") (pin "1") (pinfunction "1_1") (pintype "passive"))
      (node (ref "C5") (pin "2") (pinfunction "2_2") (pintype "passive"))
      (node (ref "C6") (pin "1") (pinfunction "1_1") (pintype "passive"))
      (node (ref "C7") (pin "1") (pinfunction "1_1") (pintype "passive"))
      (node (ref "C8") (pin "1") (pinfunction "1_1") (pintype "passive"))
      (node (ref "C9") (pin "2") (pinfunction "2_2") (pintype "passive"))
      (node (ref "H1") (pin "4") (pinfunction "4_4") (pintype "passive"))
      (node (ref "H2") (pin "3") (pinfunction "3_3") (pintype "passive"))
      (node (ref "KEY1") (pin "3") (pinfunction "3_3") (pintype "passive"))
      (node (ref "KEY1") (pin "4") (pinfunction "4_4") (pintype "passive"))
      (node (ref "KEY2") (pin "3") (pinfunction "3_3") (pintype "passive"))
      (node (ref "KEY2") (pin "4") (pinfunction "4_4") (pintype "passive"))
      (node (ref "KEY3") (pin "3") (pinfunction "3_3") (pintype "passive"))
      (node (ref "KEY3") (pin "4") (pinfunction "4_4") (pintype "passive"))
      (node (ref "Q1") (pin "3") (pinfunction "S_3") (pintype "passive"))
      (node (ref "Q14") (pin "3") (pinfunction "S_3") (pintype "passive"))
      (node (ref "R1") (pin "1") (pinfunction "1_1") (pintype "passive"))
      (node (ref "R37") (pin "1") (pinfunction "1_1") (pintype "passive"))
      (node (ref "R40") (pin "1") (pinfunction "1_1") (pintype "passive"))
      (node (ref "U2") (pin "16") (pinfunction "GND_16") (pintype "passive"))
      (node (ref "U3") (pin "3") (pinfunction "3_3") (pintype "passive"))
      (node (ref "U4") (pin "3") (pinfunction "3_3") (pintype "passive"))
      (node (ref "U7") (pin "1") (pinfunction "1_1") (pintype "passive"))
      (node (ref "U8") (pin "2") (pinfunction "GND_2") (pintype "passive"))
    )
    (net (code "42") (name "Net-(LED3-A)") (class "Default")
      (node (ref "LED3") (pin "2") (pinfunction "A_2") (pintype "passive"))
      (node (ref "R21") (pin "2") (pinfunction "2_2") (pintype "passive"))
    )
    (net (code "43") (name "Net-(LED4-A)") (class "Default")
      (node (ref "LED4") (pin "2") (pinfunction "A_2") (pintype "passive"))
      (node (ref "R22") (pin "2") (pinfunction "2_2") (pintype "passive"))
    )
    (net (code "44") (name "Net-(LED5-A)") (class "Default")
      (node (ref "LED5") (pin "2") (pinfunction "A_2") (pintype "passive"))
      (node (ref "R23") (pin "2") (pinfunction "2_2") (pintype "passive"))
    )
    (net (code "45") (name "Net-(Q1-D)") (class "Default")
      (node (ref "Q1") (pin "2") (pinfunction "D_2") (pintype "passive"))
      (node (ref "Q2") (pin "2") (pinfunction "D_2") (pintype "passive"))
      (node (ref "U1") (pin "1") (pinfunction "1_1") (pintype "passive"))
    )
    (net (code "46") (name "Net-(Q1-G)") (class "Default")
      (node (ref "Q1") (pin "1") (pinfunction "G_1") (pintype "passive"))
      (node (ref "R43") (pin "1") (pinfunction "1_1") (pintype "passive"))
    )
    (net (code "47") (name "Net-(Q2-G)") (class "Default")
      (node (ref "Q2") (pin "1") (pinfunction "G_1") (pintype "passive"))
      (node (ref "R44") (pin "1") (pinfunction "1_1") (pintype "passive"))
    )
    (net (code "48") (name "Net-(Q5-B)") (class "Default")
      (node (ref "Q5") (pin "1") (pinfunction "B_1") (pintype "passive"))
      (node (ref "R3") (pin "1") (pinfunction "1_1") (pintype "passive"))
    )
    (net (code "49") (name "Net-(Q5-C)") (class "Default")
      (node (ref "Q5") (pin "3") (pinfunction "C_3") (pintype "passive"))
      (node (ref "R2") (pin "2") (pinfunction "2_2") (pintype "passive"))
    )
    (net (code "50") (name "Net-(Q6-B)") (class "Default")
      (node (ref "Q6") (pin "1") (pinfunction "B_1") (pintype "passive"))
      (node (ref "R5") (pin "1") (pinfunction "1_1") (pintype "passive"))
    )
    (net (code "51") (name "Net-(Q6-C)") (class "Default")
      (node (ref "Q6") (pin "3") (pinfunction "C_3") (pintype "passive"))
      (node (ref "R4") (pin "2") (pinfunction "2_2") (pintype "passive"))
    )
    (net (code "52") (name "Net-(Q7-B)") (class "Default")
      (node (ref "Q7") (pin "1") (pinfunction "B_1") (pintype "passive"))
      (node (ref "R7") (pin "1") (pinfunction "1_1") (pintype "passive"))
    )
    (net (code "53") (name "Net-(Q7-C)") (class "Default")
      (node (ref "Q7") (pin "3") (pinfunction "C_3") (pintype "passive"))
      (node (ref "R6") (pin "2") (pinfunction "2_2") (pintype "passive"))
    )
    (net (code "54") (name "Net-(Q8-B)") (class "Default")
      (node (ref "Q8") (pin "1") (pinfunction "B_1") (pintype "passive"))
      (node (ref "R9") (pin "1") (pinfunction "1_1") (pintype "passive"))
    )
    (net (code "55") (name "Net-(Q8-C)") (class "Default")
      (node (ref "Q8") (pin "3") (pinfunction "C_3") (pintype "passive"))
      (node (ref "R8") (pin "2") (pinfunction "2_2") (pintype "passive"))
    )
    (net (code "56") (name "Net-(Q9-B)") (class "Default")
      (node (ref "Q9") (pin "1") (pinfunction "B_1") (pintype "passive"))
      (node (ref "R11") (pin "1") (pinfunction "1_1") (pintype "passive"))
    )
    (net (code "57") (name "Net-(Q9-C)") (class "Default")
      (node (ref "Q9") (pin "3") (pinfunction "C_3") (pintype "passive"))
      (node (ref "R10") (pin "2") (pinfunction "2_2") (pintype "passive"))
    )
    (net (code "58") (name "Net-(Q10-B)") (class "Default")
      (node (ref "Q10") (pin "1") (pinfunction "B_1") (pintype "passive"))
      (node (ref "R13") (pin "1") (pinfunction "1_1") (pintype "passive"))
    )
    (net (code "59") (name "Net-(Q10-C)") (class "Default")
      (node (ref "Q10") (pin "3") (pinfunction "C_3") (pintype "passive"))
      (node (ref "R12") (pin "2") (pinfunction "2_2") (pintype "passive"))
    )
    (net (code "60") (name "Net-(Q11-B)") (class "Default")
      (node (ref "Q11") (pin "1") (pinfunction "B_1") (pintype "passive"))
      (node (ref "R15") (pin "1") (pinfunction "1_1") (pintype "passive"))
    )
    (net (code "61") (name "Net-(Q11-C)") (class "Default")
      (node (ref "Q11") (pin "3") (pinfunction "C_3") (pintype "passive"))
      (node (ref "R14") (pin "2") (pinfunction "2_2") (pintype "passive"))
    )
    (net (code "62") (name "Net-(Q12-B)") (class "Default")
      (node (ref "Q12") (pin "1") (pinfunction "B_1") (pintype "passive"))
      (node (ref "R17") (pin "1") (pinfunction "1_1") (pintype "passive"))
    )
    (net (code "63") (name "Net-(Q12-C)") (class "Default")
      (node (ref "Q12") (pin "3") (pinfunction "C_3") (pintype "passive"))
      (node (ref "R16") (pin "2") (pinfunction "2_2") (pintype "passive"))
    )
    (net (code "64") (name "Net-(Q13-D)") (class "Default")
      (node (ref "Q13") (pin "2") (pinfunction "D_2") (pintype "passive"))
      (node (ref "Q14") (pin "2") (pinfunction "D_2") (pintype "passive"))
      (node (ref "U1") (pin "2") (pinfunction "2_2") (pintype "passive"))
    )
    (net (code "65") (name "Net-(Q13-G)") (class "Default")
      (node (ref "Q13") (pin "1") (pinfunction "G_1") (pintype "passive"))
      (node (ref "R41") (pin "2") (pinfunction "2_2") (pintype "passive"))
    )
    (net (code "66") (name "Net-(Q14-G)") (class "Default")
      (node (ref "Q14") (pin "1") (pinfunction "G_1") (pintype "passive"))
      (node (ref "R42") (pin "2") (pinfunction "2_2") (pintype "passive"))
    )
    (net (code "67") (name "Net-(R33-Pad2)") (class "Default")
      (node (ref "R33") (pin "2") (pinfunction "2_2") (pintype "passive"))
      (node (ref "U3") (pin "2") (pinfunction "2_2") (pintype "passive"))
    )
    (net (code "68") (name "Net-(R34-Pad2)") (class "Default")
      (node (ref "R34") (pin "2") (pinfunction "2_2") (pintype "passive"))
      (node (ref "U4") (pin "2") (pinfunction "2_2") (pintype "passive"))
    )
    (net (code "69") (name "Net-(R35-Pad2)") (class "Default")
      (node (ref "R35") (pin "2") (pinfunction "2_2") (pintype "passive"))
      (node (ref "U5") (pin "2") (pinfunction "2_2") (pintype "passive"))
    )
    (net (code "70") (name "Net-(R36-Pad2)") (class "Default")
      (node (ref "R36") (pin "2") (pinfunction "2_2") (pintype "passive"))
      (node (ref "U6") (pin "2") (pinfunction "2_2") (pintype "passive"))
    )
    (net (code "71") (name "Net-(U2-RST)") (class "Default")
      (node (ref "C1") (pin "1") (pinfunction "1_1") (pintype "passive"))
      (node (ref "R1") (pin "2") (pinfunction "2_2") (pintype "passive"))
      (node (ref "U2") (pin "4") (pinfunction "RST_4") (pintype "passive"))
    )
    (net (code "72") (name "Net-(U2-XTAL1)") (class "Default")
      (node (ref "C3") (pin "2") (pinfunction "2_2") (pintype "passive"))
      (node (ref "U2") (pin "15") (pinfunction "XTAL1_15") (pintype "passive"))
      (node (ref "X1") (pin "1") (pinfunction "OSC1_1") (pintype "passive"))
    )
    (net (code "73") (name "Net-(U2-XTAL2)") (class "Default")
      (node (ref "C2") (pin "2") (pinfunction "2_2") (pintype "passive"))
      (node (ref "U2") (pin "14") (pinfunction "XTAL2_14") (pintype "passive"))
      (node (ref "X1") (pin "2") (pinfunction "OSC2_2") (pintype "passive"))
    )
    (net (code "74") (name "VCC") (class "Default")
      (node (ref "C4") (pin "2") (pinfunction "2_2") (pintype "passive"))
      (node (ref "C5") (pin "1") (pinfunction "1_1") (pintype "passive"))
      (node (ref "Q13") (pin "3") (pinfunction "S_3") (pintype "passive"))
      (node (ref "Q2") (pin "3") (pinfunction "S_3") (pintype "passive"))
      (node (ref "R38") (pin "2") (pinfunction "2_2") (pintype "passive"))
      (node (ref "R39") (pin "2") (pinfunction "2_2") (pintype "passive"))
      (node (ref "U5") (pin "4") (pinfunction "4_4") (pintype "passive"))
      (node (ref "U6") (pin "4") (pinfunction "4_4") (pintype "passive"))
      (node (ref "U7") (pin "2") (pinfunction "2_2") (pintype "passive"))
      (node (ref "U8") (pin "1") (pinfunction "IN_1") (pintype "passive"))
    )
    (net (code "75") (name "unconnected-(U2-ALE#-Pad27)") (class "Default")
      (node (ref "U2") (pin "27") (pinfunction "ALE#_27") (pintype "passive+no_connect"))
    )
    (net (code "76") (name "unconnected-(U2-INT0{slash}P3.2-Pad8)") (class "Default")
      (node (ref "U2") (pin "8") (pinfunction "INT0/P3.2_8") (pintype "passive+no_connect"))
    )
    (net (code "77") (name "unconnected-(U2-INT1{slash}P3.3-Pad9)") (class "Default")
      (node (ref "U2") (pin "9") (pinfunction "INT1/P3.3_9") (pintype "passive+no_connect"))
    )
    (net (code "78") (name "unconnected-(U2-P1.7-Pad3)") (class "Default")
      (node (ref "U2") (pin "3") (pinfunction "P1.7_3") (pintype "passive+no_connect"))
    )
    (net (code "79") (name "unconnected-(U2-P4.0-Pad17)") (class "Default")
      (node (ref "U2") (pin "17") (pinfunction "P4.0_17") (pintype "passive+no_connect"))
    )
    (net (code "80") (name "unconnected-(U2-P4.1-Pad28)") (class "Default")
      (node (ref "U2") (pin "28") (pinfunction "P4.1_28") (pintype "passive+no_connect"))
    )
    (net (code "81") (name "unconnected-(U2-P4.2{slash}INT3-Pad39)") (class "Default")
      (node (ref "U2") (pin "39") (pinfunction "P4.2/INT3_39") (pintype "passive+no_connect"))
    )
    (net (code "82") (name "unconnected-(U2-P4.3{slash}INT2-Pad6)") (class "Default")
      (node (ref "U2") (pin "6") (pinfunction "P4.3/INT2_6") (pintype "passive+no_connect"))
    )
    (net (code "83") (name "unconnected-(U2-PSEN#-Pad26)") (class "Default")
      (node (ref "U2") (pin "26") (pinfunction "PSEN#_26") (pintype "passive+no_connect"))
    )
    (net (code "84") (name "unconnected-(U2-T0{slash}P3.4-Pad10)") (class "Default")
      (node (ref "U2") (pin "10") (pinfunction "T0/P3.4_10") (pintype "passive+no_connect"))
    )
    (net (code "85") (name "unconnected-(U2-T1{slash}P3.5-Pad11)") (class "Default")
      (node (ref "U2") (pin "11") (pinfunction "T1/P3.5_11") (pintype "passive+no_connect"))
    )
  )
)
